# IGBT_B.net
KiCad netlist of a schematic drawn in Altium Designer
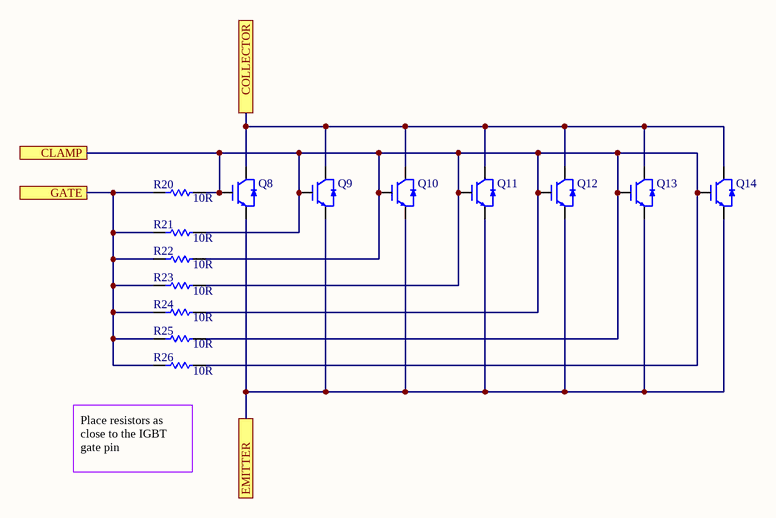
[diagram p0: IGBT_B.SchDoc]

(export (version "E")
  (design (tool "Eeschema 10.0.6"))
  (components
    (comp (ref "Q8")
      (value "STGB30V60DF")
      (footprint "DPAK2_IGBT")
      (description "IGBT 600V 60A 258W D2PAK")
      (fields (field (name "MANUFACTURER") "STMicroelectronics"))
      (libsource (lib "InverterSCHLib") (part "STGB30V60DF"))
    )
    (comp (ref "Q9")
      (value "STGB30V60DF")
      (footprint "DPAK2_IGBT")
      (description "IGBT 600V 60A 258W D2PAK")
      (fields (field (name "MANUFACTURER") "STMicroelectronics"))
      (libsource (lib "InverterSCHLib") (part "STGB30V60DF"))
    )
    (comp (ref "Q10")
      (value "STGB30V60DF")
      (footprint "DPAK2_IGBT")
      (description "IGBT 600V 60A 258W D2PAK")
      (fields (field (name "MANUFACTURER") "STMicroelectronics"))
      (libsource (lib "InverterSCHLib") (part "STGB30V60DF"))
    )
    (comp (ref "Q11")
      (value "STGB30V60DF")
      (footprint "DPAK2_IGBT")
      (description "IGBT 600V 60A 258W D2PAK")
      (fields (field (name "MANUFACTURER") "STMicroelectronics"))
      (libsource (lib "InverterSCHLib") (part "STGB30V60DF"))
    )
    (comp (ref "Q12")
      (value "STGB30V60DF")
      (footprint "DPAK2_IGBT")
      (description "IGBT 600V 60A 258W D2PAK")
      (fields (field (name "MANUFACTURER") "STMicroelectronics"))
      (libsource (lib "InverterSCHLib") (part "STGB30V60DF"))
    )
    (comp (ref "Q13")
      (value "STGB30V60DF")
      (footprint "DPAK2_IGBT")
      (description "IGBT 600V 60A 258W D2PAK")
      (fields (field (name "MANUFACTURER") "STMicroelectronics"))
      (libsource (lib "InverterSCHLib") (part "STGB30V60DF"))
    )
    (comp (ref "Q14")
      (value "STGB30V60DF")
      (footprint "DPAK2_IGBT")
      (description "IGBT 600V 60A 258W D2PAK")
      (fields (field (name "MANUFACTURER") "STMicroelectronics"))
      (libsource (lib "InverterSCHLib") (part "STGB30V60DF"))
    )
    (comp (ref "R20")
      (value "10R")
      (footprint "RES-0603")
      (description "RES SMD 10 OHM 1% 1/10W 0603")
      (fields
        (field (name "MANUFACTURER") "Yageo")
        (field (name "MANUFACTURER PART NUMBER") "RC0603FR-0710RL")
      )
      (libsource (lib "InverterSCHLib") (part "0603-10R"))
    )
    (comp (ref "R21")
      (value "10R")
      (footprint "RES-0603")
      (description "RES SMD 10 OHM 1% 1/10W 0603")
      (fields
        (field (name "MANUFACTURER") "Yageo")
        (field (name "MANUFACTURER PART NUMBER") "RC0603FR-0710RL")
      )
      (libsource (lib "InverterSCHLib") (part "0603-10R"))
    )
    (comp (ref "R22")
      (value "10R")
      (footprint "RES-0603")
      (description "RES SMD 10 OHM 1% 1/10W 0603")
      (fields
        (field (name "MANUFACTURER") "Yageo")
        (field (name "MANUFACTURER PART NUMBER") "RC0603FR-0710RL")
      )
      (libsource (lib "InverterSCHLib") (part "0603-10R"))
    )
    (comp (ref "R23")
      (value "10R")
      (footprint "RES-0603")
      (description "RES SMD 10 OHM 1% 1/10W 0603")
      (fields
        (field (name "MANUFACTURER") "Yageo")
        (field (name "MANUFACTURER PART NUMBER") "RC0603FR-0710RL")
      )
      (libsource (lib "InverterSCHLib") (part "0603-10R"))
    )
    (comp (ref "R24")
      (value "10R")
      (footprint "RES-0603")
      (description "RES SMD 10 OHM 1% 1/10W 0603")
      (fields
        (field (name "MANUFACTURER") "Yageo")
        (field (name "MANUFACTURER PART NUMBER") "RC0603FR-0710RL")
      )
      (libsource (lib "InverterSCHLib") (part "0603-10R"))
    )
    (comp (ref "R25")
      (value "10R")
      (footprint "RES-0603")
      (description "RES SMD 10 OHM 1% 1/10W 0603")
      (fields
        (field (name "MANUFACTURER") "Yageo")
        (field (name "MANUFACTURER PART NUMBER") "RC0603FR-0710RL")
      )
      (libsource (lib "InverterSCHLib") (part "0603-10R"))
    )
    (comp (ref "R26")
      (value "10R")
      (footprint "RES-0603")
      (description "RES SMD 10 OHM 1% 1/10W 0603")
      (fields
        (field (name "MANUFACTURER") "Yageo")
        (field (name "MANUFACTURER PART NUMBER") "RC0603FR-0710RL")
      )
      (libsource (lib "InverterSCHLib") (part "0603-10R"))
    )
  )
  (nets
    (net (code "1") (name "/CLAMP") (class "Default")
      (node (ref "Q10") (pin "1") (pinfunction "1_1") (pintype "passive"))
      (node (ref "Q11") (pin "1") (pinfunction "1_1") (pintype "passive"))
      (node (ref "Q12") (pin "1") (pinfunction "1_1") (pintype "passive"))
      (node (ref "Q13") (pin "1") (pinfunction "1_1") (pintype "passive"))
      (node (ref "Q14") (pin "1") (pinfunction "1_1") (pintype "passive"))
      (node (ref "Q8") (pin "1") (pinfunction "1_1") (pintype "passive"))
      (node (ref "Q9") (pin "1") (pinfunction "1_1") (pintype "passive"))
      (node (ref "R20") (pin "2") (pinfunction "2_2") (pintype "passive"))
      (node (ref "R21") (pin "2") (pinfunction "2_2") (pintype "passive"))
      (node (ref "R22") (pin "2") (pinfunction "2_2") (pintype "passive"))
      (node (ref "R23") (pin "2") (pinfunction "2_2") (pintype "passive"))
      (node (ref "R24") (pin "2") (pinfunction "2_2") (pintype "passive"))
      (node (ref "R25") (pin "2") (pinfunction "2_2") (pintype "passive"))
      (node (ref "R26") (pin "2") (pinfunction "2_2") (pintype "passive"))
    )
    (net (code "2") (name "/COLLECTOR") (class "Default")
      (node (ref "Q10") (pin "2") (pinfunction "2_2") (pintype "passive"))
      (node (ref "Q11") (pin "2") (pinfunction "2_2") (pintype "passive"))
      (node (ref "Q12") (pin "2") (pinfunction "2_2") (pintype "passive"))
      (node (ref "Q13") (pin "2") (pinfunction "2_2") (pintype "passive"))
      (node (ref "Q14") (pin "2") (pinfunction "2_2") (pintype "passive"))
      (node (ref "Q8") (pin "2") (pinfunction "2_2") (pintype "passive"))
      (node (ref "Q9") (pin "2") (pinfunction "2_2") (pintype "passive"))
    )
    (net (code "3") (name "/EMITTER") (class "Default")
      (node (ref "Q10") (pin "3") (pinfunction "3_3") (pintype "passive"))
      (node (ref "Q11") (pin "3") (pinfunction "3_3") (pintype "passive"))
      (node (ref "Q12") (pin "3") (pinfunction "3_3") (pintype "passive"))
      (node (ref "Q13") (pin "3") (pinfunction "3_3") (pintype "passive"))
      (node (ref "Q14") (pin "3") (pinfunction "3_3") (pintype "passive"))
      (node (ref "Q8") (pin "3") (pinfunction "3_3") (pintype "passive"))
      (node (ref "Q9") (pin "3") (pinfunction "3_3") (pintype "passive"))
    )
    (net (code "4") (name "/GATE") (class "Default")
      (node (ref "R20") (pin "1") (pinfunction "1_1") (pintype "passive"))
      (node (ref "R21") (pin "1") (pinfunction "1_1") (pintype "passive"))
      (node (ref "R22") (pin "1") (pinfunction "1_1") (pintype "passive"))
      (node (ref "R23") (pin "1") (pinfunction "1_1") (pintype "passive"))
      (node (ref "R24") (pin "1") (pinfunction "1_1") (pintype "passive"))
      (node (ref "R25") (pin "1") (pinfunction "1_1") (pintype "passive"))
      (node (ref "R26") (pin "1") (pinfunction "1_1") (pintype "passive"))
    )
  )
)
